# OK6010_DB_PWR.net
KiCad netlist of a schematic drawn in Altium Designer
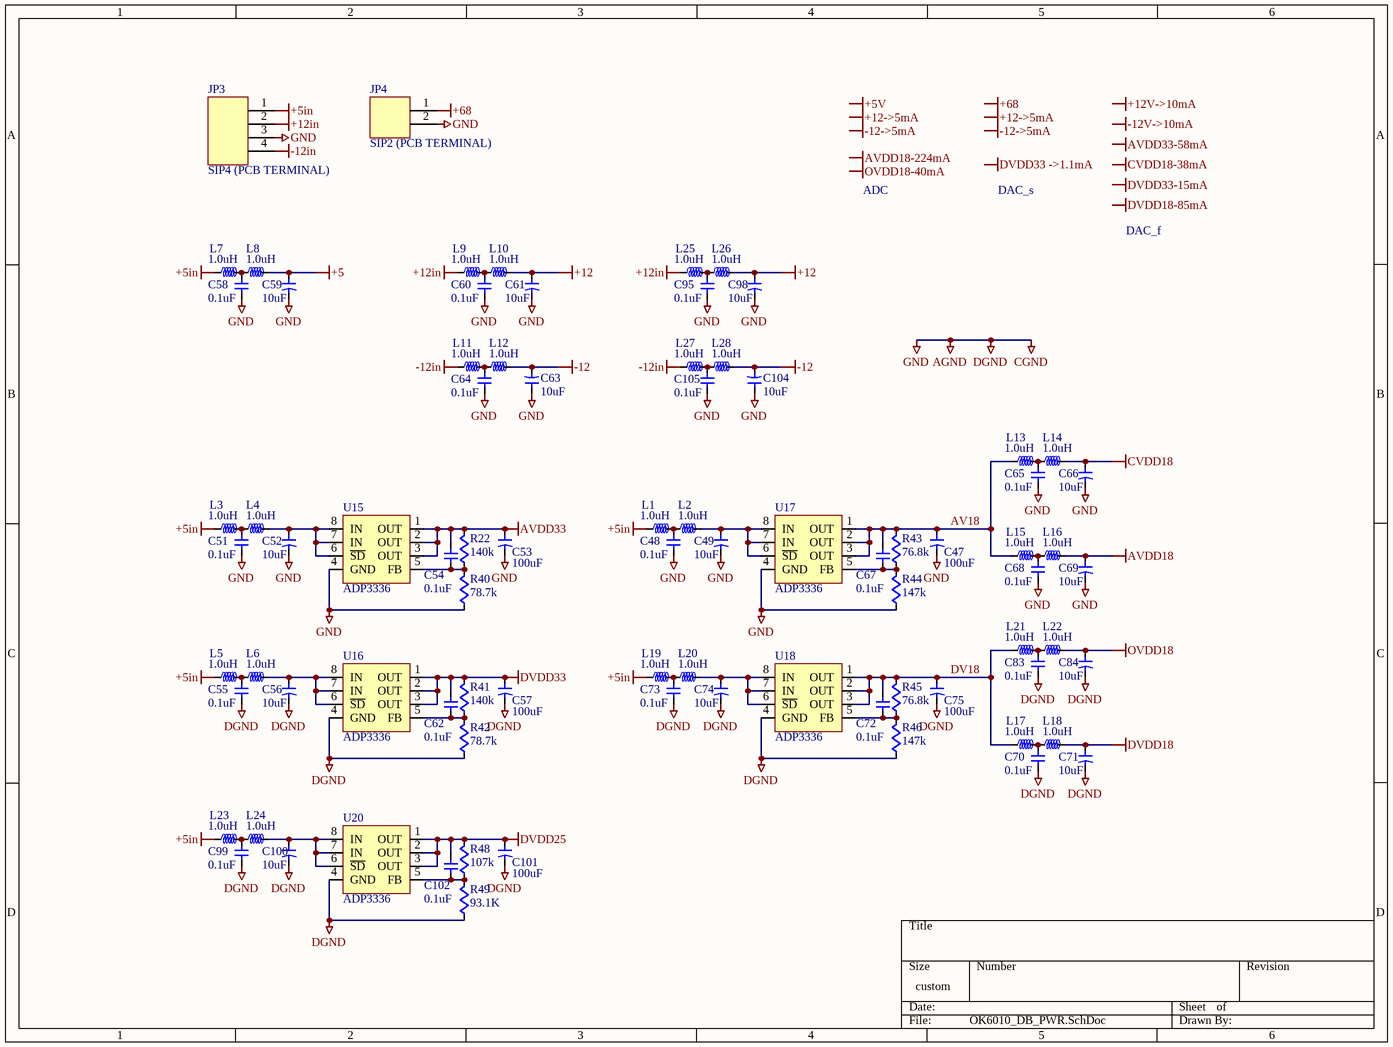
[diagram p0: OK6010_DB_PWR.SchDoc]

(export (version "E")
  (design (tool "Eeschema 10.0.6"))
  (components
    (comp (ref "C47")
      (value "100uF")
      (footprint "1206")
      (description "capacitor")
      (fields
        (field (name "MANUFACTURER") "TDK Corporation")
        (field (name "MANUFACTURER PART NUMBER") "C3216X5R0J107M")
      )
      (libsource (lib "Device02_remote") (part "CAPACITOR_SM"))
    )
    (comp (ref "C48")
      (value "0.1uF")
      (footprint "0603w")
      (description "capacitor")
      (fields
        (field (name "MANUFACTURER") "Kemet")
        (field (name "MANUFACTURER PART NUMBER") "C0603C104K3RACTU")
      )
      (libsource (lib "Device02_remote") (part "CAP_SM"))
    )
    (comp (ref "C49")
      (value "10uF")
      (footprint "1206")
      (description "ELECTROLYTIC capacitor")
      (fields
        (field (name "MANUFACTURER") "Nichicon")
        (field (name "MANUFACTURER PART NUMBER") "F971C106MAA")
      )
      (libsource (lib "Device02_remote") (part "CAPACITOR_SM"))
    )
    (comp (ref "C51")
      (value "0.1uF")
      (footprint "0603w")
      (description "capacitor")
      (fields
        (field (name "MANUFACTURER") "Kemet")
        (field (name "MANUFACTURER PART NUMBER") "C0603C104K3RACTU")
      )
      (libsource (lib "Device02_remote") (part "CAP_SM"))
    )
    (comp (ref "C52")
      (value "10uF")
      (footprint "1206")
      (description "ELECTROLYTIC capacitor")
      (fields
        (field (name "MANUFACTURER") "Nichicon")
        (field (name "MANUFACTURER PART NUMBER") "F971C106MAA")
      )
      (libsource (lib "Device02_remote") (part "CAPACITOR_SM"))
    )
    (comp (ref "C53")
      (value "100uF")
      (footprint "1206")
      (description "capacitor")
      (fields
        (field (name "MANUFACTURER") "TDK Corporation")
        (field (name "MANUFACTURER PART NUMBER") "C3216X5R0J107M")
      )
      (libsource (lib "Device02_remote") (part "CAPACITOR_SM"))
    )
    (comp (ref "C54")
      (value "0.1uF")
      (footprint "0603w")
      (description "capacitor")
      (fields
        (field (name "MANUFACTURER") "Kemet")
        (field (name "MANUFACTURER PART NUMBER") "C0603C104K3RACTU")
      )
      (libsource (lib "Device02_remote") (part "CAP_SM"))
    )
    (comp (ref "C55")
      (value "0.1uF")
      (footprint "0603w")
      (description "capacitor")
      (fields
        (field (name "MANUFACTURER") "Kemet")
        (field (name "MANUFACTURER PART NUMBER") "C0603C104K3RACTU")
      )
      (libsource (lib "Device02_remote") (part "CAP_SM"))
    )
    (comp (ref "C56")
      (value "10uF")
      (footprint "1206")
      (description "ELECTROLYTIC capacitor")
      (fields
        (field (name "MANUFACTURER") "Nichicon")
        (field (name "MANUFACTURER PART NUMBER") "F971C106MAA")
      )
      (libsource (lib "Device02_remote") (part "CAPACITOR_SM"))
    )
    (comp (ref "C57")
      (value "100uF")
      (footprint "1206")
      (description "capacitor")
      (fields
        (field (name "MANUFACTURER") "TDK Corporation")
        (field (name "MANUFACTURER PART NUMBER") "C3216X5R0J107M")
      )
      (libsource (lib "Device02_remote") (part "CAPACITOR_SM"))
    )
    (comp (ref "C58")
      (value "0.1uF")
      (footprint "0603w")
      (description "capacitor")
      (fields
        (field (name "MANUFACTURER") "Kemet")
        (field (name "MANUFACTURER PART NUMBER") "C0603C104K3RACTU")
      )
      (libsource (lib "Device02_remote") (part "CAP_SM"))
    )
    (comp (ref "C59")
      (value "10uF")
      (footprint "1206")
      (description "ELECTROLYTIC capacitor")
      (fields
        (field (name "MANUFACTURER") "Nichicon")
        (field (name "MANUFACTURER PART NUMBER") "F971C106MAA")
      )
      (libsource (lib "Device02_remote") (part "CAPACITOR_SM"))
    )
    (comp (ref "C60")
      (value "0.1uF")
      (footprint "0603w")
      (description "capacitor")
      (fields
        (field (name "MANUFACTURER") "Kemet")
        (field (name "MANUFACTURER PART NUMBER") "C0603C104K3RACTU")
      )
      (libsource (lib "Device02_remote") (part "CAP_SM"))
    )
    (comp (ref "C61")
      (value "10uF")
      (footprint "1206")
      (description "ELECTROLYTIC capacitor")
      (fields
        (field (name "MANUFACTURER") "Nichicon")
        (field (name "MANUFACTURER PART NUMBER") "F971C106MAA")
      )
      (libsource (lib "Device02_remote") (part "CAPACITOR_SM"))
    )
    (comp (ref "C62")
      (value "0.1uF")
      (footprint "0603w")
      (description "capacitor")
      (fields
        (field (name "MANUFACTURER") "Kemet")
        (field (name "MANUFACTURER PART NUMBER") "C0603C104K3RACTU")
      )
      (libsource (lib "Device02_remote") (part "CAP_SM"))
    )
    (comp (ref "C63")
      (value "10uF")
      (footprint "1206")
      (description "ELECTROLYTIC capacitor")
      (fields
        (field (name "MANUFACTURER") "Nichicon")
        (field (name "MANUFACTURER PART NUMBER") "F971C106MAA")
      )
      (libsource (lib "Device02_remote") (part "CAPACITOR_SM"))
    )
    (comp (ref "C64")
      (value "0.1uF")
      (footprint "0603w")
      (description "capacitor")
      (fields
        (field (name "MANUFACTURER") "Kemet")
        (field (name "MANUFACTURER PART NUMBER") "C0603C104K3RACTU")
      )
      (libsource (lib "Device02_remote") (part "CAP_SM"))
    )
    (comp (ref "C65")
      (value "0.1uF")
      (footprint "0603w")
      (description "capacitor")
      (fields
        (field (name "MANUFACTURER") "Kemet")
        (field (name "MANUFACTURER PART NUMBER") "C0603C104K3RACTU")
      )
      (libsource (lib "Device02_remote") (part "CAP_SM"))
    )
    (comp (ref "C66")
      (value "10uF")
      (footprint "1206")
      (description "ELECTROLYTIC capacitor")
      (fields
        (field (name "MANUFACTURER") "Nichicon")
        (field (name "MANUFACTURER PART NUMBER") "F971C106MAA")
      )
      (libsource (lib "Device02_remote") (part "CAPACITOR_SM"))
    )
    (comp (ref "C67")
      (value "0.1uF")
      (footprint "0603w")
      (description "capacitor")
      (fields
        (field (name "MANUFACTURER") "Kemet")
        (field (name "MANUFACTURER PART NUMBER") "C0603C104K3RACTU")
      )
      (libsource (lib "Device02_remote") (part "CAP_SM"))
    )
    (comp (ref "C68")
      (value "0.1uF")
      (footprint "0603w")
      (description "capacitor")
      (fields
        (field (name "MANUFACTURER") "Kemet")
        (field (name "MANUFACTURER PART NUMBER") "C0603C104K3RACTU")
      )
      (libsource (lib "Device02_remote") (part "CAP_SM"))
    )
    (comp (ref "C69")
      (value "10uF")
      (footprint "1206")
      (description "ELECTROLYTIC capacitor")
      (fields
        (field (name "MANUFACTURER") "Nichicon")
        (field (name "MANUFACTURER PART NUMBER") "F971C106MAA")
      )
      (libsource (lib "Device02_remote") (part "CAPACITOR_SM"))
    )
    (comp (ref "C70")
      (value "0.1uF")
      (footprint "0603w")
      (description "capacitor")
      (fields
        (field (name "MANUFACTURER") "Kemet")
        (field (name "MANUFACTURER PART NUMBER") "C0603C104K3RACTU")
      )
      (libsource (lib "Device02_remote") (part "CAP_SM"))
    )
    (comp (ref "C71")
      (value "10uF")
      (footprint "1206")
      (description "ELECTROLYTIC capacitor")
      (fields
        (field (name "MANUFACTURER") "Nichicon")
        (field (name "MANUFACTURER PART NUMBER") "F971C106MAA")
      )
      (libsource (lib "Device02_remote") (part "CAPACITOR_SM"))
    )
    (comp (ref "C72")
      (value "0.1uF")
      (footprint "0603w")
      (description "capacitor")
      (fields
        (field (name "MANUFACTURER") "Kemet")
        (field (name "MANUFACTURER PART NUMBER") "C0603C104K3RACTU")
      )
      (libsource (lib "Device02_remote") (part "CAP_SM"))
    )
    (comp (ref "C73")
      (value "0.1uF")
      (footprint "0603w")
      (description "capacitor")
      (fields
        (field (name "MANUFACTURER") "Kemet")
        (field (name "MANUFACTURER PART NUMBER") "C0603C104K3RACTU")
      )
      (libsource (lib "Device02_remote") (part "CAP_SM"))
    )
    (comp (ref "C74")
      (value "10uF")
      (footprint "1206")
      (description "ELECTROLYTIC capacitor")
      (fields
        (field (name "MANUFACTURER") "Nichicon")
        (field (name "MANUFACTURER PART NUMBER") "F971C106MAA")
      )
      (libsource (lib "Device02_remote") (part "CAPACITOR_SM"))
    )
    (comp (ref "C75")
      (value "100uF")
      (footprint "1206")
      (description "capacitor")
      (fields
        (field (name "MANUFACTURER") "TDK Corporation")
        (field (name "MANUFACTURER PART NUMBER") "C3216X5R0J107M")
      )
      (libsource (lib "Device02_remote") (part "CAPACITOR_SM"))
    )
    (comp (ref "C83")
      (value "0.1uF")
      (footprint "0603w")
      (description "capacitor")
      (fields
        (field (name "MANUFACTURER") "Kemet")
        (field (name "MANUFACTURER PART NUMBER") "C0603C104K3RACTU")
      )
      (libsource (lib "Device02_remote") (part "CAP_SM"))
    )
    (comp (ref "C84")
      (value "10uF")
      (footprint "1206")
      (description "ELECTROLYTIC capacitor")
      (fields
        (field (name "MANUFACTURER") "Nichicon")
        (field (name "MANUFACTURER PART NUMBER") "F971C106MAA")
      )
      (libsource (lib "Device02_remote") (part "CAPACITOR_SM"))
    )
    (comp (ref "C95")
      (value "0.1uF")
      (footprint "0603w")
      (description "capacitor")
      (fields
        (field (name "MANUFACTURER") "Kemet")
        (field (name "MANUFACTURER PART NUMBER") "C0603C104K3RACTU")
      )
      (libsource (lib "Device02_remote") (part "CAP_SM"))
    )
    (comp (ref "C98")
      (value "10uF")
      (footprint "1206")
      (description "ELECTROLYTIC capacitor")
      (fields
        (field (name "MANUFACTURER") "Nichicon")
        (field (name "MANUFACTURER PART NUMBER") "F971C106MAA")
      )
      (libsource (lib "Device02_remote") (part "CAPACITOR_SM"))
    )
    (comp (ref "C99")
      (value "0.1uF")
      (footprint "0603w")
      (description "capacitor")
      (fields
        (field (name "MANUFACTURER") "Kemet")
        (field (name "MANUFACTURER PART NUMBER") "C0603C104K3RACTU")
      )
      (libsource (lib "Device02_remote") (part "CAP_SM"))
    )
    (comp (ref "C100")
      (value "10uF")
      (footprint "1206")
      (description "ELECTROLYTIC capacitor")
      (fields
        (field (name "MANUFACTURER") "Nichicon")
        (field (name "MANUFACTURER PART NUMBER") "F971C106MAA")
      )
      (libsource (lib "Device02_remote") (part "CAPACITOR_SM"))
    )
    (comp (ref "C101")
      (value "100uF")
      (footprint "1206")
      (description "capacitor")
      (fields
        (field (name "MANUFACTURER") "TDK Corporation")
        (field (name "MANUFACTURER PART NUMBER") "C3216X5R0J107M")
      )
      (libsource (lib "Device02_remote") (part "CAPACITOR_SM"))
    )
    (comp (ref "C102")
      (value "0.1uF")
      (footprint "0603w")
      (description "capacitor")
      (fields
        (field (name "MANUFACTURER") "Kemet")
        (field (name "MANUFACTURER PART NUMBER") "C0603C104K3RACTU")
      )
      (libsource (lib "Device02_remote") (part "CAP_SM"))
    )
    (comp (ref "C104")
      (value "10uF")
      (footprint "1206")
      (description "ELECTROLYTIC capacitor")
      (fields
        (field (name "MANUFACTURER") "Nichicon")
        (field (name "MANUFACTURER PART NUMBER") "F971C106MAA")
      )
      (libsource (lib "Device02_remote") (part "CAPACITOR_SM"))
    )
    (comp (ref "C105")
      (value "0.1uF")
      (footprint "0603w")
      (description "capacitor")
      (fields
        (field (name "MANUFACTURER") "Kemet")
        (field (name "MANUFACTURER PART NUMBER") "C0603C104K3RACTU")
      )
      (libsource (lib "Device02_remote") (part "CAP_SM"))
    )
    (comp (ref "JP3")
      (value "SIP4 (PCB TERMINAL)")
      (footprint "SIP4MOLEX")
      (description "4 pin molex connector")
      (fields
        (field (name "MANUFACTURER") "Molex Inc")
        (field (name "MANUFACTURER PART NUMBER") "22-29-2041")
      )
      (libsource (lib "Device02_remote") (part "SIP4 (PCB TERMINAL)"))
    )
    (comp (ref "JP4")
      (value "SIP2 (PCB TERMINAL)")
      (footprint "SIP2MOLEX")
      (description "2 pin molex connector")
      (fields
        (field (name "MANUFACTURER") "Molex Inc")
        (field (name "MANUFACTURER PART NUMBER") "22-29-2021")
      )
      (libsource (lib "Device02_remote") (part "SIP2 (PCB TERMINAL)"))
    )
    (comp (ref "L1")
      (value "1.0uH")
      (footprint "1210")
      (description "inductor")
      (fields
        (field (name "MANUFACTURER") "Murata Electronics North America")
        (field (name "MANUFACTURER PART NUMBER") "LQH32CN1R0M23L")
      )
      (libsource (lib "altium-import") (part "root_0_INDUCTOR_SM_"))
    )
    (comp (ref "L2")
      (value "1.0uH")
      (footprint "1210")
      (description "inductor")
      (fields
        (field (name "MANUFACTURER") "Murata Electronics North America")
        (field (name "MANUFACTURER PART NUMBER") "LQH32CN1R0M23L")
      )
      (libsource (lib "altium-import") (part "root_0_INDUCTOR_SM_"))
    )
    (comp (ref "L3")
      (value "1.0uH")
      (footprint "0805")
      (description "inductor")
      (fields
        (field (name "MANUFACTURER") "Murata Electronics North America")
        (field (name "MANUFACTURER PART NUMBER") "LQM21FN1R0N00D")
      )
      (libsource (lib "altium-import") (part "root_0_INDUCTOR_SM_"))
    )
    (comp (ref "L4")
      (value "1.0uH")
      (footprint "0805")
      (description "inductor")
      (fields
        (field (name "MANUFACTURER") "Murata Electronics North America")
        (field (name "MANUFACTURER PART NUMBER") "LQM21FN1R0N00D")
      )
      (libsource (lib "altium-import") (part "root_0_INDUCTOR_SM_"))
    )
    (comp (ref "L5")
      (value "1.0uH")
      (footprint "0805")
      (description "inductor")
      (fields
        (field (name "MANUFACTURER") "Murata Electronics North America")
        (field (name "MANUFACTURER PART NUMBER") "LQM21FN1R0N00D")
      )
      (libsource (lib "altium-import") (part "root_0_INDUCTOR_SM_"))
    )
    (comp (ref "L6")
      (value "1.0uH")
      (footprint "0805")
      (description "inductor")
      (fields
        (field (name "MANUFACTURER") "Murata Electronics North America")
        (field (name "MANUFACTURER PART NUMBER") "LQM21FN1R0N00D")
      )
      (libsource (lib "altium-import") (part "root_0_INDUCTOR_SM_"))
    )
    (comp (ref "L7")
      (value "1.0uH")
      (footprint "1210")
      (description "inductor")
      (fields
        (field (name "MANUFACTURER") "Murata Electronics North America")
        (field (name "MANUFACTURER PART NUMBER") "LQH32CN1R0M23L")
      )
      (libsource (lib "altium-import") (part "root_0_INDUCTOR_SM_"))
    )
    (comp (ref "L8")
      (value "1.0uH")
      (footprint "1210")
      (description "inductor")
      (fields
        (field (name "MANUFACTURER") "Murata Electronics North America")
        (field (name "MANUFACTURER PART NUMBER") "LQH32CN1R0M23L")
      )
      (libsource (lib "altium-import") (part "root_0_INDUCTOR_SM_"))
    )
    (comp (ref "L9")
      (value "1.0uH")
      (footprint "1210")
      (description "inductor")
      (fields
        (field (name "MANUFACTURER") "Murata Electronics North America")
        (field (name "MANUFACTURER PART NUMBER") "LQH32CN1R0M23L")
      )
      (libsource (lib "altium-import") (part "root_0_INDUCTOR_SM_"))
    )
    (comp (ref "L10")
      (value "1.0uH")
      (footprint "1210")
      (description "inductor")
      (fields
        (field (name "MANUFACTURER") "Murata Electronics North America")
        (field (name "MANUFACTURER PART NUMBER") "LQH32CN1R0M23L")
      )
      (libsource (lib "altium-import") (part "root_0_INDUCTOR_SM_"))
    )
    (comp (ref "L11")
      (value "1.0uH")
      (footprint "1210")
      (description "inductor")
      (fields
        (field (name "MANUFACTURER") "Murata Electronics North America")
        (field (name "MANUFACTURER PART NUMBER") "LQH32CN1R0M23L")
      )
      (libsource (lib "altium-import") (part "root_0_INDUCTOR_SM_"))
    )
    (comp (ref "L12")
      (value "1.0uH")
      (footprint "1210")
      (description "inductor")
      (fields
        (field (name "MANUFACTURER") "Murata Electronics North America")
        (field (name "MANUFACTURER PART NUMBER") "LQH32CN1R0M23L")
      )
      (libsource (lib "altium-import") (part "root_0_INDUCTOR_SM_"))
    )
    (comp (ref "L13")
      (value "1.0uH")
      (footprint "0805")
      (description "inductor")
      (fields
        (field (name "MANUFACTURER") "Murata Electronics North America")
        (field (name "MANUFACTURER PART NUMBER") "LQM21FN1R0N00D")
      )
      (libsource (lib "altium-import") (part "root_0_INDUCTOR_SM_"))
    )
    (comp (ref "L14")
      (value "1.0uH")
      (footprint "0805")
      (description "inductor")
      (fields
        (field (name "MANUFACTURER") "Murata Electronics North America")
        (field (name "MANUFACTURER PART NUMBER") "LQM21FN1R0N00D")
      )
      (libsource (lib "altium-import") (part "root_0_INDUCTOR_SM_"))
    )
    (comp (ref "L15")
      (value "1.0uH")
      (footprint "1210")
      (description "inductor")
      (fields
        (field (name "MANUFACTURER") "Murata Electronics North America")
        (field (name "MANUFACTURER PART NUMBER") "LQH32CN1R0M23L")
      )
      (libsource (lib "altium-import") (part "root_0_INDUCTOR_SM_"))
    )
    (comp (ref "L16")
      (value "1.0uH")
      (footprint "1210")
      (description "inductor")
      (fields
        (field (name "MANUFACTURER") "Murata Electronics North America")
        (field (name "MANUFACTURER PART NUMBER") "LQH32CN1R0M23L")
      )
      (libsource (lib "altium-import") (part "root_0_INDUCTOR_SM_"))
    )
    (comp (ref "L17")
      (value "1.0uH")
      (footprint "0805")
      (description "inductor")
      (fields
        (field (name "MANUFACTURER") "Murata Electronics North America")
        (field (name "MANUFACTURER PART NUMBER") "LQM21FN1R0N00D")
      )
      (libsource (lib "altium-import") (part "root_0_INDUCTOR_SM_"))
    )
    (comp (ref "L18")
      (value "1.0uH")
      (footprint "0805")
      (description "inductor")
      (fields
        (field (name "MANUFACTURER") "Murata Electronics North America")
        (field (name "MANUFACTURER PART NUMBER") "LQM21FN1R0N00D")
      )
      (libsource (lib "altium-import") (part "root_0_INDUCTOR_SM_"))
    )
    (comp (ref "L19")
      (value "1.0uH")
      (footprint "0805")
      (description "inductor")
      (fields
        (field (name "MANUFACTURER") "Murata Electronics North America")
        (field (name "MANUFACTURER PART NUMBER") "LQM21FN1R0N00D")
      )
      (libsource (lib "altium-import") (part "root_0_INDUCTOR_SM_"))
    )
    (comp (ref "L20")
      (value "1.0uH")
      (footprint "0805")
      (description "inductor")
      (fields
        (field (name "MANUFACTURER") "Murata Electronics North America")
        (field (name "MANUFACTURER PART NUMBER") "LQM21FN1R0N00D")
      )
      (libsource (lib "altium-import") (part "root_0_INDUCTOR_SM_"))
    )
    (comp (ref "L21")
      (value "1.0uH")
      (footprint "0805")
      (description "inductor")
      (fields
        (field (name "MANUFACTURER") "Murata Electronics North America")
        (field (name "MANUFACTURER PART NUMBER") "LQM21FN1R0N00D")
      )
      (libsource (lib "altium-import") (part "root_0_INDUCTOR_SM_"))
    )
    (comp (ref "L22")
      (value "1.0uH")
      (footprint "0805")
      (description "inductor")
      (fields
        (field (name "MANUFACTURER") "Murata Electronics North America")
        (field (name "MANUFACTURER PART NUMBER") "LQM21FN1R0N00D")
      )
      (libsource (lib "altium-import") (part "root_0_INDUCTOR_SM_"))
    )
    (comp (ref "L23")
      (value "1.0uH")
      (footprint "0805")
      (description "inductor")
      (fields
        (field (name "MANUFACTURER") "Murata Electronics North America")
        (field (name "MANUFACTURER PART NUMBER") "LQM21FN1R0N00D")
      )
      (libsource (lib "altium-import") (part "root_0_INDUCTOR_SM_"))
    )
    (comp (ref "L24")
      (value "1.0uH")
      (footprint "0805")
      (description "inductor")
      (fields
        (field (name "MANUFACTURER") "Murata Electronics North America")
        (field (name "MANUFACTURER PART NUMBER") "LQM21FN1R0N00D")
      )
      (libsource (lib "altium-import") (part "root_0_INDUCTOR_SM_"))
    )
    (comp (ref "L25")
      (value "1.0uH")
      (footprint "1210")
      (description "inductor")
      (fields
        (field (name "MANUFACTURER") "Murata Electronics North America")
        (field (name "MANUFACTURER PART NUMBER") "LQH32CN1R0M23L")
      )
      (libsource (lib "altium-import") (part "root_0_INDUCTOR_SM_"))
    )
    (comp (ref "L26")
      (value "1.0uH")
      (footprint "1210")
      (description "inductor")
      (fields
        (field (name "MANUFACTURER") "Murata Electronics North America")
        (field (name "MANUFACTURER PART NUMBER") "LQH32CN1R0M23L")
      )
      (libsource (lib "altium-import") (part "root_0_INDUCTOR_SM_"))
    )
    (comp (ref "L27")
      (value "1.0uH")
      (footprint "1210")
      (description "inductor")
      (fields
        (field (name "MANUFACTURER") "Murata Electronics North America")
        (field (name "MANUFACTURER PART NUMBER") "LQH32CN1R0M23L")
      )
      (libsource (lib "altium-import") (part "root_0_INDUCTOR_SM_"))
    )
    (comp (ref "L28")
      (value "1.0uH")
      (footprint "1210")
      (description "inductor")
      (fields
        (field (name "MANUFACTURER") "Murata Electronics North America")
        (field (name "MANUFACTURER PART NUMBER") "LQH32CN1R0M23L")
      )
      (libsource (lib "altium-import") (part "root_0_INDUCTOR_SM_"))
    )
    (comp (ref "R22")
      (value "140k")
      (footprint "0603w")
      (description "resistor")
      (fields
        (field (name "MANUFACTURER") "Yageo")
        (field (name "MANUFACTURER PART NUMBER") "RC0603FR-07140KL")
      )
      (libsource (lib "Device02_remote") (part "RES_SM"))
    )
    (comp (ref "R40")
      (value "78.7k")
      (footprint "0603w")
      (description "resistor")
      (fields
        (field (name "MANUFACTURER") "Yageo")
        (field (name "MANUFACTURER PART NUMBER") "RC0603FR-0778K7L")
      )
      (libsource (lib "Device02_remote") (part "RES_SM"))
    )
    (comp (ref "R41")
      (value "140k")
      (footprint "0603w")
      (description "resistor")
      (fields
        (field (name "MANUFACTURER") "Yageo")
        (field (name "MANUFACTURER PART NUMBER") "RC0603FR-07140KL")
      )
      (libsource (lib "Device02_remote") (part "RES_SM"))
    )
    (comp (ref "R42")
      (value "78.7k")
      (footprint "0603w")
      (description "resistor")
      (fields
        (field (name "MANUFACTURER") "Yageo")
        (field (name "MANUFACTURER PART NUMBER") "RC0603FR-0778K7L")
      )
      (libsource (lib "Device02_remote") (part "RES_SM"))
    )
    (comp (ref "R43")
      (value "76.8k")
      (footprint "0603w")
      (description "resistor")
      (fields
        (field (name "MANUFACTURER") "Yageo")
        (field (name "MANUFACTURER PART NUMBER") "RC0603FR-0776K8L")
      )
      (libsource (lib "Device02_remote") (part "RES_SM"))
    )
    (comp (ref "R44")
      (value "147k")
      (footprint "0603w")
      (description "resistor")
      (fields
        (field (name "MANUFACTURER") "Yageo")
        (field (name "MANUFACTURER PART NUMBER") "RC0603FR-07147KL")
      )
      (libsource (lib "Device02_remote") (part "RES_SM"))
    )
    (comp (ref "R45")
      (value "76.8k")
      (footprint "0603w")
      (description "resistor")
      (fields
        (field (name "MANUFACTURER") "Yageo")
        (field (name "MANUFACTURER PART NUMBER") "RC0603FR-0776K8L")
      )
      (libsource (lib "Device02_remote") (part "RES_SM"))
    )
    (comp (ref "R46")
      (value "147k")
      (footprint "0603w")
      (description "resistor")
      (fields
        (field (name "MANUFACTURER") "Yageo")
        (field (name "MANUFACTURER PART NUMBER") "RC0603FR-07147KL")
      )
      (libsource (lib "Device02_remote") (part "RES_SM"))
    )
    (comp (ref "R48")
      (value "107k")
      (footprint "0603w")
      (description "resistor")
      (fields
        (field (name "MANUFACTURER") "Yageo")
        (field (name "MANUFACTURER PART NUMBER") "RC0603FR-07107KL")
      )
      (libsource (lib "Device02_remote") (part "RES_SM"))
    )
    (comp (ref "R49")
      (value "93.1K")
      (footprint "0603w")
      (description "resistor")
      (fields
        (field (name "MANUFACTURER") "Yageo")
        (field (name "MANUFACTURER PART NUMBER") "RC0603FR-0793K1L")
      )
      (libsource (lib "Device02_remote") (part "RES_SM"))
    )
    (comp (ref "U15")
      (value "ADP3336")
      (footprint "MSOP08")
      (description "regulator")
      (fields
        (field (name "MANUFACTURER") "Analog Devices Inc")
        (field (name "MANUFACTURER PART NUMBER") "ADP3336ARMZ-REEL7")
      )
      (libsource (lib "Device02_remote") (part "ADP3336"))
    )
    (comp (ref "U16")
      (value "ADP3336")
      (footprint "MSOP08")
      (description "regulator")
      (fields
        (field (name "MANUFACTURER") "Analog Devices Inc")
        (field (name "MANUFACTURER PART NUMBER") "ADP3336ARMZ-REEL7")
      )
      (libsource (lib "Device02_remote") (part "ADP3336"))
    )
    (comp (ref "U17")
      (value "ADP3336")
      (footprint "MSOP08")
      (description "regulator")
      (fields
        (field (name "MANUFACTURER") "Analog Devices Inc")
        (field (name "MANUFACTURER PART NUMBER") "ADP3336ARMZ-REEL7")
      )
      (libsource (lib "Device02_remote") (part "ADP3336"))
    )
    (comp (ref "U18")
      (value "ADP3336")
      (footprint "MSOP08")
      (description "regulator")
      (fields
        (field (name "MANUFACTURER") "Analog Devices Inc")
        (field (name "MANUFACTURER PART NUMBER") "ADP3336ARMZ-REEL7")
      )
      (libsource (lib "Device02_remote") (part "ADP3336"))
    )
    (comp (ref "U20")
      (value "ADP3336")
      (footprint "MSOP08")
      (description "regulator")
      (fields
        (field (name "MANUFACTURER") "Analog Devices Inc")
        (field (name "MANUFACTURER PART NUMBER") "ADP3336ARMZ-REEL7")
      )
      (libsource (lib "Device02_remote") (part "ADP3336"))
    )
  )
  (nets
    (net (code "1") (name "+5") (class "Default")
      (node (ref "C59") (pin "1") (pintype "passive"))
      (node (ref "L8") (pin "2") (pintype "passive"))
    )
    (net (code "3") (name "+5in") (class "Default")
      (node (ref "JP3") (pin "1") (pintype "passive"))
      (node (ref "L1") (pin "1") (pintype "passive"))
      (node (ref "L19") (pin "1") (pintype "passive"))
      (node (ref "L23") (pin "1") (pintype "passive"))
      (node (ref "L3") (pin "1") (pintype "passive"))
      (node (ref "L5") (pin "1") (pintype "passive"))
      (node (ref "L7") (pin "1") (pintype "passive"))
    )
    (net (code "4") (name "+12") (class "Default")
      (node (ref "C61") (pin "1") (pintype "passive"))
      (node (ref "C98") (pin "1") (pintype "passive"))
      (node (ref "L10") (pin "2") (pintype "passive"))
      (node (ref "L26") (pin "2") (pintype "passive"))
    )
    (net (code "7") (name "+12in") (class "Default")
      (node (ref "JP3") (pin "2") (pintype "passive"))
      (node (ref "L25") (pin "1") (pintype "passive"))
      (node (ref "L9") (pin "1") (pintype "passive"))
    )
    (net (code "8") (name "+68") (class "Default") (node (ref "JP4") (pin "1") (pintype "passive")))
    (net (code "9") (name "-12") (class "Default")
      (node (ref "C104") (pin "2") (pintype "passive"))
      (node (ref "C63") (pin "2") (pintype "passive"))
      (node (ref "L12") (pin "2") (pintype "passive"))
      (node (ref "L28") (pin "2") (pintype "passive"))
    )
    (net (code "12") (name "-12in") (class "Default")
      (node (ref "JP3") (pin "4") (pintype "passive"))
      (node (ref "L11") (pin "1") (pintype "passive"))
      (node (ref "L27") (pin "1") (pintype "passive"))
    )
    (net (code "13") (name "/AV18") (class "Default")
      (node (ref "C47") (pin "1") (pintype "passive"))
      (node (ref "C67") (pin "1") (pintype "passive"))
      (node (ref "L13") (pin "1") (pintype "passive"))
      (node (ref "L15") (pin "1") (pintype "passive"))
      (node (ref "R43") (pin "2") (pintype "passive"))
      (node (ref "U17") (pin "1") (pinfunction "OUT_1") (pintype "passive"))
      (node (ref "U17") (pin "2") (pinfunction "OUT_2") (pintype "passive"))
      (node (ref "U17") (pin "3") (pinfunction "OUT_3") (pintype "passive"))
    )
    (net (code "14") (name "/DV18") (class "Default")
      (node (ref "C72") (pin "1") (pintype "passive"))
      (node (ref "C75") (pin "1") (pintype "passive"))
      (node (ref "L17") (pin "1") (pintype "passive"))
      (node (ref "L21") (pin "1") (pintype "passive"))
      (node (ref "R45") (pin "2") (pintype "passive"))
      (node (ref "U18") (pin "1") (pinfunction "OUT_1") (pintype "passive"))
      (node (ref "U18") (pin "2") (pinfunction "OUT_2") (pintype "passive"))
      (node (ref "U18") (pin "3") (pinfunction "OUT_3") (pintype "passive"))
    )
    (net (code "15") (name "AGND") (class "Default")
      (node (ref "C100") (pin "2") (pintype "passive"))
      (node (ref "C101") (pin "2") (pintype "passive"))
      (node (ref "C104") (pin "1") (pintype "passive"))
      (node (ref "C105") (pin "2") (pintype "passive"))
      (node (ref "C47") (pin "2") (pintype "passive"))
      (node (ref "C48") (pin "2") (pintype "passive"))
      (node (ref "C49") (pin "2") (pintype "passive"))
      (node (ref "C51") (pin "2") (pintype "passive"))
      (node (ref "C52") (pin "2") (pintype "passive"))
      (node (ref "C53") (pin "2") (pintype "passive"))
      (node (ref "C55") (pin "2") (pintype "passive"))
      (node (ref "C56") (pin "2") (pintype "passive"))
      (node (ref "C57") (pin "2") (pintype "passive"))
      (node (ref "C58") (pin "2") (pintype "passive"))
      (node (ref "C59") (pin "2") (pintype "passive"))
      (node (ref "C60") (pin "2") (pintype "passive"))
      (node (ref "C61") (pin "2") (pintype "passive"))
      (node (ref "C63") (pin "1") (pintype "passive"))
      (node (ref "C64") (pin "2") (pintype "passive"))
      (node (ref "C65") (pin "2") (pintype "passive"))
      (node (ref "C66") (pin "2") (pintype "passive"))
      (node (ref "C68") (pin "2") (pintype "passive"))
      (node (ref "C69") (pin "2") (pintype "passive"))
      (node (ref "C70") (pin "2") (pintype "passive"))
      (node (ref "C71") (pin "2") (pintype "passive"))
      (node (ref "C73") (pin "2") (pintype "passive"))
      (node (ref "C74") (pin "2") (pintype "passive"))
      (node (ref "C75") (pin "2") (pintype "passive"))
      (node (ref "C83") (pin "2") (pintype "passive"))
      (node (ref "C84") (pin "2") (pintype "passive"))
      (node (ref "C95") (pin "2") (pintype "passive"))
      (node (ref "C98") (pin "2") (pintype "passive"))
      (node (ref "C99") (pin "2") (pintype "passive"))
      (node (ref "JP3") (pin "3") (pintype "passive"))
      (node (ref "JP4") (pin "2") (pintype "passive"))
      (node (ref "R40") (pin "1") (pintype "passive"))
      (node (ref "R42") (pin "1") (pintype "passive"))
      (node (ref "R44") (pin "1") (pintype "passive"))
      (node (ref "R46") (pin "1") (pintype "passive"))
      (node (ref "R49") (pin "1") (pintype "passive"))
      (node (ref "U15") (pin "4") (pinfunction "GND_4") (pintype "passive"))
      (node (ref "U16") (pin "4") (pinfunction "GND_4") (pintype "passive"))
      (node (ref "U17") (pin "4") (pinfunction "GND_4") (pintype "passive"))
      (node (ref "U18") (pin "4") (pinfunction "GND_4") (pintype "passive"))
      (node (ref "U20") (pin "4") (pinfunction "GND_4") (pintype "passive"))
    )
    (net (code "16") (name "AVDD18") (class "Default")
      (node (ref "C69") (pin "1") (pintype "passive"))
      (node (ref "L16") (pin "2") (pintype "passive"))
    )
    (net (code "18") (name "AVDD33") (class "Default")
      (node (ref "C53") (pin "1") (pintype "passive"))
      (node (ref "C54") (pin "1") (pintype "passive"))
      (node (ref "R22") (pin "2") (pintype "passive"))
      (node (ref "U15") (pin "1") (pinfunction "OUT_1") (pintype "passive"))
      (node (ref "U15") (pin "2") (pinfunction "OUT_2") (pintype "passive"))
      (node (ref "U15") (pin "3") (pinfunction "OUT_3") (pintype "passive"))
    )
    (net (code "20") (name "CVDD18") (class "Default")
      (node (ref "C66") (pin "1") (pintype "passive"))
      (node (ref "L14") (pin "2") (pintype "passive"))
    )
    (net (code "22") (name "DVDD18") (class "Default")
      (node (ref "C71") (pin "1") (pintype "passive"))
      (node (ref "L18") (pin "2") (pintype "passive"))
    )
    (net (code "24") (name "DVDD25") (class "Default")
      (node (ref "C101") (pin "1") (pintype "passive"))
      (node (ref "C102") (pin "1") (pintype "passive"))
      (node (ref "R48") (pin "2") (pintype "passive"))
      (node (ref "U20") (pin "1") (pinfunction "OUT_1") (pintype "passive"))
      (node (ref "U20") (pin "2") (pinfunction "OUT_2") (pintype "passive"))
      (node (ref "U20") (pin "3") (pinfunction "OUT_3") (pintype "passive"))
    )
    (net (code "25") (name "DVDD33") (class "Default")
      (node (ref "C57") (pin "1") (pintype "passive"))
      (node (ref "C62") (pin "1") (pintype "passive"))
      (node (ref "R41") (pin "2") (pintype "passive"))
      (node (ref "U16") (pin "1") (pinfunction "OUT_1") (pintype "passive"))
      (node (ref "U16") (pin "2") (pinfunction "OUT_2") (pintype "passive"))
      (node (ref "U16") (pin "3") (pinfunction "OUT_3") (pintype "passive"))
    )
    (net (code "28") (name "Net-(C48-Pad1)") (class "Default")
      (node (ref "C48") (pin "1") (pintype "passive"))
      (node (ref "L1") (pin "2") (pintype "passive"))
      (node (ref "L2") (pin "1") (pintype "passive"))
    )
    (net (code "29") (name "Net-(C51-Pad1)") (class "Default")
      (node (ref "C51") (pin "1") (pintype "passive"))
      (node (ref "L3") (pin "2") (pintype "passive"))
      (node (ref "L4") (pin "1") (pintype "passive"))
    )
    (net (code "30") (name "Net-(C55-Pad1)") (class "Default")
      (node (ref "C55") (pin "1") (pintype "passive"))
      (node (ref "L5") (pin "2") (pintype "passive"))
      (node (ref "L6") (pin "1") (pintype "passive"))
    )
    (net (code "31") (name "Net-(C58-Pad1)") (class "Default")
      (node (ref "C58") (pin "1") (pintype "passive"))
      (node (ref "L7") (pin "2") (pintype "passive"))
      (node (ref "L8") (pin "1") (pintype "passive"))
    )
    (net (code "32") (name "Net-(C60-Pad1)") (class "Default")
      (node (ref "C60") (pin "1") (pintype "passive"))
      (node (ref "L10") (pin "1") (pintype "passive"))
      (node (ref "L9") (pin "2") (pintype "passive"))
    )
    (net (code "33") (name "Net-(C64-Pad1)") (class "Default")
      (node (ref "C64") (pin "1") (pintype "passive"))
      (node (ref "L11") (pin "2") (pintype "passive"))
      (node (ref "L12") (pin "1") (pintype "passive"))
    )
    (net (code "34") (name "Net-(C65-Pad1)") (class "Default")
      (node (ref "C65") (pin "1") (pintype "passive"))
      (node (ref "L13") (pin "2") (pintype "passive"))
      (node (ref "L14") (pin "1") (pintype "passive"))
    )
    (net (code "35") (name "Net-(C68-Pad1)") (class "Default")
      (node (ref "C68") (pin "1") (pintype "passive"))
      (node (ref "L15") (pin "2") (pintype "passive"))
      (node (ref "L16") (pin "1") (pintype "passive"))
    )
    (net (code "36") (name "Net-(C70-Pad1)") (class "Default")
      (node (ref "C70") (pin "1") (pintype "passive"))
      (node (ref "L17") (pin "2") (pintype "passive"))
      (node (ref "L18") (pin "1") (pintype "passive"))
    )
    (net (code "37") (name "Net-(C73-Pad1)") (class "Default")
      (node (ref "C73") (pin "1") (pintype "passive"))
      (node (ref "L19") (pin "2") (pintype "passive"))
      (node (ref "L20") (pin "1") (pintype "passive"))
    )
    (net (code "38") (name "Net-(C83-Pad1)") (class "Default")
      (node (ref "C83") (pin "1") (pintype "passive"))
      (node (ref "L21") (pin "2") (pintype "passive"))
      (node (ref "L22") (pin "1") (pintype "passive"))
    )
    (net (code "39") (name "Net-(C95-Pad1)") (class "Default")
      (node (ref "C95") (pin "1") (pintype "passive"))
      (node (ref "L25") (pin "2") (pintype "passive"))
      (node (ref "L26") (pin "1") (pintype "passive"))
    )
    (net (code "40") (name "Net-(C99-Pad1)") (class "Default")
      (node (ref "C99") (pin "1") (pintype "passive"))
      (node (ref "L23") (pin "2") (pintype "passive"))
      (node (ref "L24") (pin "1") (pintype "passive"))
    )
    (net (code "41") (name "Net-(C105-Pad1)") (class "Default")
      (node (ref "C105") (pin "1") (pintype "passive"))
      (node (ref "L27") (pin "2") (pintype "passive"))
      (node (ref "L28") (pin "1") (pintype "passive"))
    )
    (net (code "42") (name "Net-(U15-FB)") (class "Default")
      (node (ref "C54") (pin "2") (pintype "passive"))
      (node (ref "R22") (pin "1") (pintype "passive"))
      (node (ref "R40") (pin "2") (pintype "passive"))
      (node (ref "U15") (pin "5") (pinfunction "FB_5") (pintype "passive"))
    )
    (net (code "43") (name "Net-(U15-~{SD})") (class "Default")
      (node (ref "C52") (pin "1") (pintype "passive"))
      (node (ref "L4") (pin "2") (pintype "passive"))
      (node (ref "U15") (pin "6") (pinfunction "~{SD}_6") (pintype "passive"))
      (node (ref "U15") (pin "7") (pinfunction "IN_7") (pintype "passive"))
      (node (ref "U15") (pin "8") (pinfunction "IN_8") (pintype "passive"))
    )
    (net (code "44") (name "Net-(U16-FB)") (class "Default")
      (node (ref "C62") (pin "2") (pintype "passive"))
      (node (ref "R41") (pin "1") (pintype "passive"))
      (node (ref "R42") (pin "2") (pintype "passive"))
      (node (ref "U16") (pin "5") (pinfunction "FB_5") (pintype "passive"))
    )
    (net (code "45") (name "Net-(U16-~{SD})") (class "Default")
      (node (ref "C56") (pin "1") (pintype "passive"))
      (node (ref "L6") (pin "2") (pintype "passive"))
      (node (ref "U16") (pin "6") (pinfunction "~{SD}_6") (pintype "passive"))
      (node (ref "U16") (pin "7") (pinfunction "IN_7") (pintype "passive"))
      (node (ref "U16") (pin "8") (pinfunction "IN_8") (pintype "passive"))
    )
    (net (code "46") (name "Net-(U17-FB)") (class "Default")
      (node (ref "C67") (pin "2") (pintype "passive"))
      (node (ref "R43") (pin "1") (pintype "passive"))
      (node (ref "R44") (pin "2") (pintype "passive"))
      (node (ref "U17") (pin "5") (pinfunction "FB_5") (pintype "passive"))
    )
    (net (code "47") (name "Net-(U17-~{SD})") (class "Default")
      (node (ref "C49") (pin "1") (pintype "passive"))
      (node (ref "L2") (pin "2") (pintype "passive"))
      (node (ref "U17") (pin "6") (pinfunction "~{SD}_6") (pintype "passive"))
      (node (ref "U17") (pin "7") (pinfunction "IN_7") (pintype "passive"))
      (node (ref "U17") (pin "8") (pinfunction "IN_8") (pintype "passive"))
    )
    (net (code "48") (name "Net-(U18-FB)") (class "Default")
      (node (ref "C72") (pin "2") (pintype "passive"))
      (node (ref "R45") (pin "1") (pintype "passive"))
      (node (ref "R46") (pin "2") (pintype "passive"))
      (node (ref "U18") (pin "5") (pinfunction "FB_5") (pintype "passive"))
    )
    (net (code "49") (name "Net-(U18-~{SD})") (class "Default")
      (node (ref "C74") (pin "1") (pintype "passive"))
      (node (ref "L20") (pin "2") (pintype "passive"))
      (node (ref "U18") (pin "6") (pinfunction "~{SD}_6") (pintype "passive"))
      (node (ref "U18") (pin "7") (pinfunction "IN_7") (pintype "passive"))
      (node (ref "U18") (pin "8") (pinfunction "IN_8") (pintype "passive"))
    )
    (net (code "50") (name "Net-(U20-FB)") (class "Default")
      (node (ref "C102") (pin "2") (pintype "passive"))
      (node (ref "R48") (pin "1") (pintype "passive"))
      (node (ref "R49") (pin "2") (pintype "passive"))
      (node (ref "U20") (pin "5") (pinfunction "FB_5") (pintype "passive"))
    )
    (net (code "51") (name "Net-(U20-~{SD})") (class "Default")
      (node (ref "C100") (pin "1") (pintype "passive"))
      (node (ref "L24") (pin "2") (pintype "passive"))
      (node (ref "U20") (pin "6") (pinfunction "~{SD}_6") (pintype "passive"))
      (node (ref "U20") (pin "7") (pinfunction "IN_7") (pintype "passive"))
      (node (ref "U20") (pin "8") (pinfunction "IN_8") (pintype "passive"))
    )
    (net (code "52") (name "OVDD18") (class "Default")
      (node (ref "C84") (pin "1") (pintype "passive"))
      (node (ref "L22") (pin "2") (pintype "passive"))
    )
  )
)
